# button_peripheral.net
KiCad netlist of a schematic drawn in Altium Designer
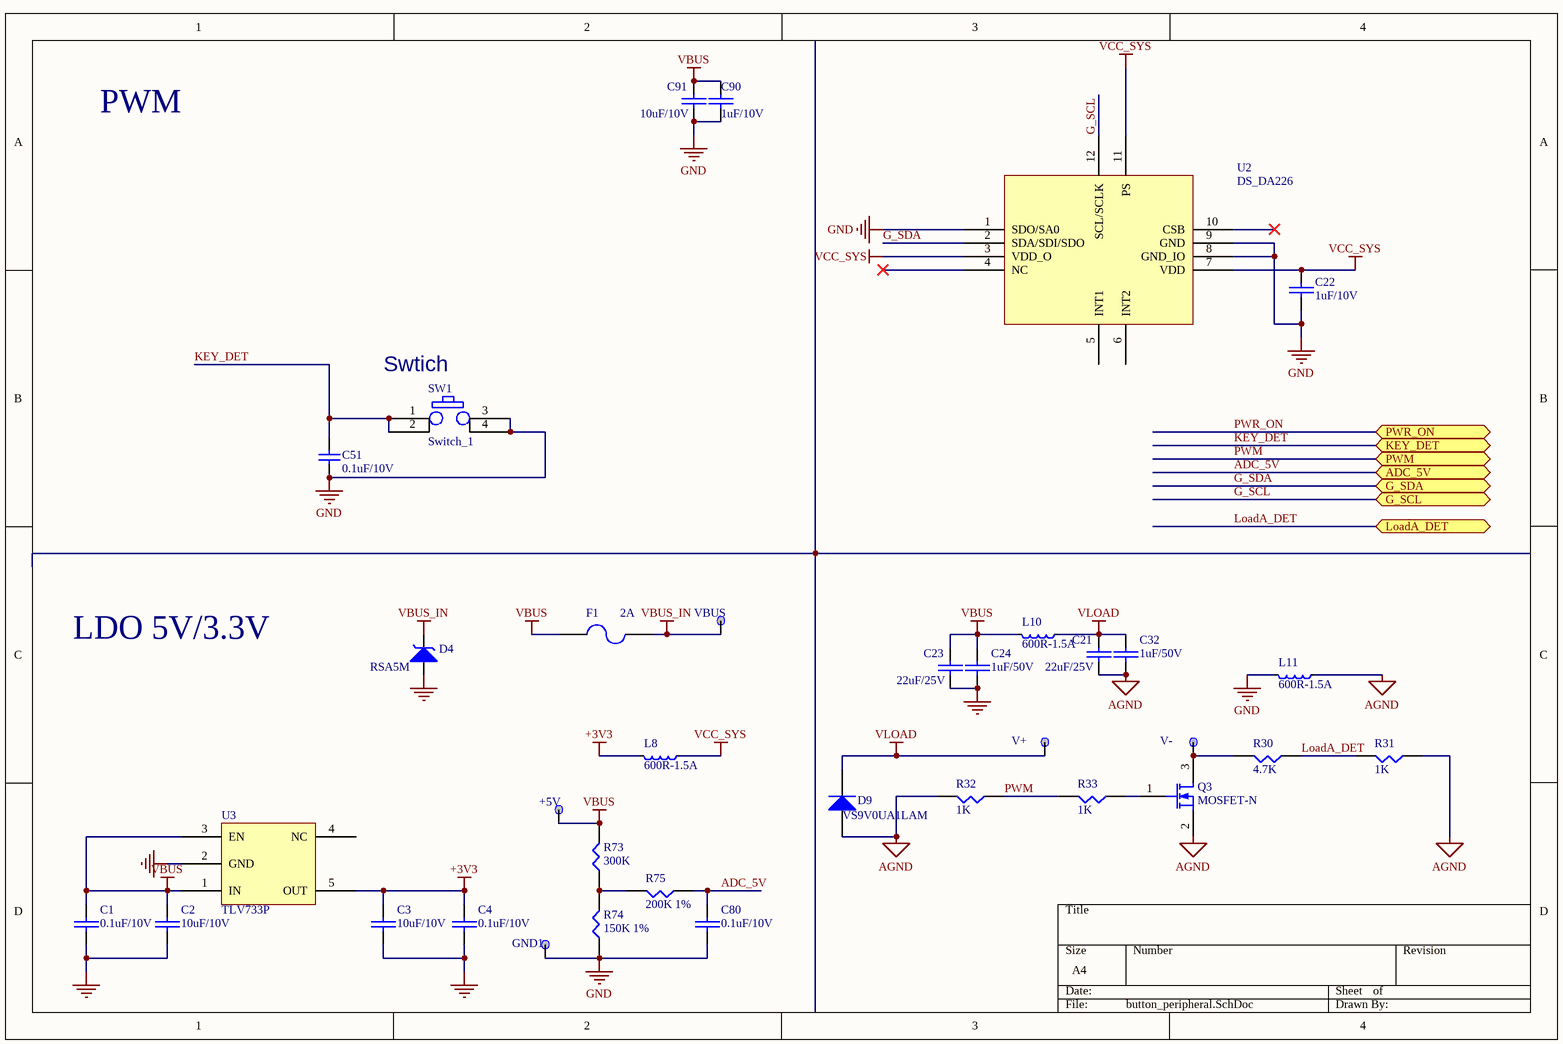
[diagram p0: button_peripheral.SchDoc]

(export (version "E")
  (design (tool "Eeschema 10.0.6"))
  (components
    (comp (ref "+5V") (value "TP") (footprint "TESTPOINT2") (libsource (lib "Almos") (part "TP")))
    (comp (ref "C1")
      (value "0.1uF/10V")
      (footprint "0402C")
      (description "厂家：Murata，型号：GRM155R71A104KA01D")
      (libsource (lib "*") (part "CAP"))
    )
    (comp (ref "C2")
      (value "10uF/10V")
      (footprint "0603C")
      (description "厂家：Murata，型号：GRM188R61A106KE69D")
      (libsource (lib "*") (part "CAP"))
    )
    (comp (ref "C3")
      (value "10uF/10V")
      (footprint "0603C")
      (description "厂家：Murata，型号：GRM188R61A106KE69D")
      (libsource (lib "*") (part "CAP"))
    )
    (comp (ref "C4")
      (value "0.1uF/10V")
      (footprint "0402C")
      (description "厂家：Murata，型号：GRM155R71A104KA01D")
      (libsource (lib "*") (part "CAP"))
    )
    (comp (ref "C21")
      (value "22uF/25V")
      (footprint "0603C")
      (description "厂家：Murata，型号：GRM188R61A106KE69D")
      (libsource (lib "*") (part "CAP"))
    )
    (comp (ref "C22")
      (value "1uF/10V")
      (footprint "0402C")
      (description "厂家：Murata，型号：GRM155R71A104KA01D")
      (libsource (lib "*") (part "CAP"))
    )
    (comp (ref "C23")
      (value "22uF/25V")
      (footprint "0603C")
      (description "厂家：Murata，型号：GRM188R61A106KE69D")
      (libsource (lib "*") (part "CAP"))
    )
    (comp (ref "C24")
      (value "1uF/50V")
      (footprint "0402C")
      (description "厂家：Murata，型号：GRM155R71A104KA01D")
      (libsource (lib "*") (part "CAP"))
    )
    (comp (ref "C32")
      (value "1uF/50V")
      (footprint "0402C")
      (description "厂家：Murata，型号：GRM155R71A104KA01D")
      (libsource (lib "*") (part "CAP"))
    )
    (comp (ref "C51")
      (value "0.1uF/10V")
      (footprint "0402C")
      (description "Capacitor")
      (fields (field (name "PUBLISHER") "Altium Limited"))
      (libsource (lib "Miscellaneous Devices") (part "CAP"))
    )
    (comp (ref "C80")
      (value "0.1uF/10V")
      (footprint "0402C")
      (description "厂家：Murata，型号：GRM155R71A104KA01D")
      (libsource (lib "*") (part "CAP"))
    )
    (comp (ref "C90")
      (value "1uF/10V")
      (footprint "0402C")
      (description "厂家：Murata，型号：GRM188R61A106KE69D")
      (libsource (lib "*") (part "CAP"))
    )
    (comp (ref "C91")
      (value "10uF/10V")
      (footprint "TAN_0603")
      (description "厂家：Murata，型号：GRM188R61A106KE69D")
      (libsource (lib "*") (part "CAP"))
    )
    (comp (ref "D4")
      (value "RSA5M")
      (footprint "SOD-123")
      (description "厂家：ROHM，型号：VMNZC6.8CST2RA")
      (libsource (lib "CCS801 VOC") (part "ESD_1"))
    )
    (comp (ref "D9")
      (value "VS9V0UA1LAM")
      (footprint "SOD_128")
      (description "High Conductance Fast Diode")
      (libsource (lib "Tools") (part "Diode 1N4148"))
    )
    (comp (ref "F1")
      (value "2A")
      (footprint "1206-FUSE - duplicate")
      (description "厂家：万瑞和，型号：smd1206-200")
      (libsource (lib "*") (part "FUSE2"))
    )
    (comp (ref "GND1") (value "TP") (footprint "TESTPOINT_PAD") (libsource (lib "Almos") (part "TP")))
    (comp (ref "L8")
      (value "600R-1.5A")
      (footprint "L_0603")
      (description "High frequency chip inductor ±5%")
      (fields
        (field (name "PART NUMBER") "L0402-27n")
        (field (name "MANUFACTURER") "Murata")
        (field (name "PUBLISHER") "Nordic Semiconductor")
      )
      (libsource (lib "Nordic Passive DB") (part "IND"))
    )
    (comp (ref "L10")
      (value "600R-1.5A")
      (footprint "L_0603")
      (description "High frequency chip inductor ±5%")
      (fields
        (field (name "PART NUMBER") "L0402-27n")
        (field (name "MANUFACTURER") "Murata")
        (field (name "PUBLISHER") "Nordic Semiconductor")
      )
      (libsource (lib "Nordic Passive DB") (part "IND"))
    )
    (comp (ref "L11")
      (value "600R-1.5A")
      (footprint "L_0603")
      (description "High frequency chip inductor ±5%")
      (fields
        (field (name "PART NUMBER") "L0402-27n")
        (field (name "MANUFACTURER") "Murata")
        (field (name "PUBLISHER") "Nordic Semiconductor")
      )
      (libsource (lib "Nordic Passive DB") (part "IND"))
    )
    (comp (ref "Q3")
      (value "MOSFET-N")
      (footprint "TSMT3")
      (description "N-Channel MOSFET")
      (fields (field (name "PUBLISHER") "Altium Limited"))
      (libsource (lib "常用sch库") (part "MOSFET-N"))
    )
    (comp (ref "R30")
      (value "4.7K")
      (footprint "0402R")
      (description "厂家：Yageo，型号：RC0402FR-0720RL")
      (libsource (lib "*") (part "RES1"))
    )
    (comp (ref "R31")
      (value "1K")
      (footprint "0402R")
      (description "厂家：Yageo，型号：RC0402FR-0720RL")
      (libsource (lib "*") (part "RES1"))
    )
    (comp (ref "R32")
      (value "1K")
      (footprint "0402R")
      (description "厂家：Yageo，型号：RC0402FR-0720RL")
      (libsource (lib "*") (part "RES1"))
    )
    (comp (ref "R33")
      (value "1K")
      (footprint "0402R")
      (description "厂家：Yageo，型号：RC0402FR-0720RL")
      (libsource (lib "*") (part "RES1"))
    )
    (comp (ref "R73")
      (value "300K")
      (footprint "0402R")
      (description "厂家：Yageo，型号：RC0402FR-0720RL")
      (libsource (lib "*") (part "RES1"))
    )
    (comp (ref "R74")
      (value "150K 1%")
      (footprint "0402R")
      (description "厂家：Yageo，型号：RC0402FR-0720RL")
      (libsource (lib "*") (part "RES1"))
    )
    (comp (ref "R75")
      (value "200K 1%")
      (footprint "0402R")
      (description "厂家：Yageo，型号：RC0402FR-0720RL")
      (libsource (lib "*") (part "RES1"))
    )
    (comp (ref "SW1")
      (value "Switch_1")
      (footprint "KEY_Panasonic")
      (description "厂家：松下，型号：EVQPLMA15")
      (libsource (lib "Amber_Display") (part "Switch_1"))
    )
    (comp (ref "U2")
      (value "DS_DA226")
      (footprint "LGA-12")
      (description "厂家：ST，型号：LIS2DH12")
      (libsource (lib "Debug Pinborad") (part "LIS2DE12"))
    )
    (comp (ref "U3") (value "TLV733P") (footprint "SOT-23-5") (libsource (lib "Tools") (part "AP3410")))
    (comp (ref "V+") (value "TP") (footprint "TESTPOINT_PAD") (libsource (lib "Almos") (part "TP")))
    (comp (ref "V-") (value "TP") (footprint "TESTPOINT_PAD") (libsource (lib "Almos") (part "TP")))
    (comp (ref "VBUS") (value "TP") (footprint "TESTPOINT_PAD") (libsource (lib "Almos") (part "TP")))
  )
  (nets
    (net (code "1") (name "+3V3") (class "Default")
      (node (ref "C3") (pin "1") (pinfunction "1_1") (pintype "passive"))
      (node (ref "C4") (pin "1") (pinfunction "1_1") (pintype "passive"))
      (node (ref "L8") (pin "2") (pinfunction "2_2") (pintype "passive"))
      (node (ref "U3") (pin "5") (pinfunction "OUT_5") (pintype "passive"))
    )
    (net (code "2") (name "/ADC_5V") (class "Default")
      (node (ref "C80") (pin "1") (pinfunction "1_1") (pintype "passive"))
      (node (ref "R75") (pin "1") (pinfunction "1_1") (pintype "passive"))
    )
    (net (code "3") (name "/G_SCL") (class "Default")
      (node (ref "U2") (pin "12") (pinfunction "SCL/SCLK_12") (pintype "passive"))
    )
    (net (code "4") (name "/G_SDA") (class "Default")
      (node (ref "U2") (pin "2") (pinfunction "SDA/SDI/SDO_2") (pintype "passive"))
    )
    (net (code "5") (name "/KEY_DET") (class "Default")
      (node (ref "C51") (pin "2") (pinfunction "2_2") (pintype "passive"))
      (node (ref "SW1") (pin "1") (pinfunction "1_1") (pintype "passive"))
      (node (ref "SW1") (pin "2") (pinfunction "2_2") (pintype "passive"))
    )
    (net (code "6") (name "/LoadA_DET") (class "Default")
      (node (ref "R30") (pin "1") (pinfunction "1_1") (pintype "passive"))
      (node (ref "R31") (pin "2") (pinfunction "2_2") (pintype "passive"))
    )
    (net (code "7") (name "/PWM") (class "Default")
      (node (ref "R32") (pin "1") (pinfunction "1_1") (pintype "passive"))
      (node (ref "R33") (pin "2") (pinfunction "2_2") (pintype "passive"))
    )
    (net (code "9") (name "AGND") (class "Default")
      (node (ref "C21") (pin "2") (pinfunction "2_2") (pintype "passive"))
      (node (ref "C32") (pin "2") (pinfunction "2_2") (pintype "passive"))
      (node (ref "D9") (pin "2") (pinfunction "A_2") (pintype "passive"))
      (node (ref "L11") (pin "1") (pinfunction "1_1") (pintype "passive"))
      (node (ref "Q3") (pin "2") (pinfunction "S_2") (pintype "passive"))
      (node (ref "R31") (pin "1") (pinfunction "1_1") (pintype "passive"))
      (node (ref "R32") (pin "2") (pinfunction "2_2") (pintype "passive"))
    )
    (net (code "10") (name "GND") (class "Default")
      (node (ref "C1") (pin "2") (pinfunction "2_2") (pintype "passive"))
      (node (ref "C2") (pin "2") (pinfunction "2_2") (pintype "passive"))
      (node (ref "C22") (pin "2") (pinfunction "2_2") (pintype "passive"))
      (node (ref "C23") (pin "2") (pinfunction "2_2") (pintype "passive"))
      (node (ref "C24") (pin "2") (pinfunction "2_2") (pintype "passive"))
      (node (ref "C3") (pin "2") (pinfunction "2_2") (pintype "passive"))
      (node (ref "C4") (pin "2") (pinfunction "2_2") (pintype "passive"))
      (node (ref "C51") (pin "1") (pinfunction "1_1") (pintype "passive"))
      (node (ref "C80") (pin "2") (pinfunction "2_2") (pintype "passive"))
      (node (ref "C90") (pin "2") (pinfunction "2_2") (pintype "passive"))
      (node (ref "C91") (pin "2") (pinfunction "2_2") (pintype "passive"))
      (node (ref "D4") (pin "2") (pinfunction "dIode2_2") (pintype "passive"))
      (node (ref "GND1") (pin "1") (pinfunction "1_1") (pintype "passive"))
      (node (ref "L11") (pin "2") (pinfunction "2_2") (pintype "passive"))
      (node (ref "R74") (pin "1") (pinfunction "1_1") (pintype "passive"))
      (node (ref "SW1") (pin "3") (pinfunction "3_3") (pintype "passive"))
      (node (ref "SW1") (pin "4") (pinfunction "4_4") (pintype "passive"))
      (node (ref "U2") (pin "1") (pinfunction "SDO/SA0_1") (pintype "passive"))
      (node (ref "U2") (pin "8") (pinfunction "GND_IO_8") (pintype "passive"))
      (node (ref "U2") (pin "9") (pinfunction "GND_9") (pintype "passive"))
      (node (ref "U3") (pin "2") (pinfunction "GND_2") (pintype "passive"))
    )
    (net (code "11") (name "Net-(Q3-D)") (class "Default")
      (node (ref "Q3") (pin "3") (pinfunction "D_3") (pintype "passive"))
      (node (ref "R30") (pin "2") (pinfunction "2_2") (pintype "passive"))
      (node (ref "V-") (pin "1") (pinfunction "1_1") (pintype "passive"))
    )
    (net (code "12") (name "Net-(Q3-G)") (class "Default")
      (node (ref "Q3") (pin "1") (pinfunction "G_1") (pintype "passive"))
      (node (ref "R33") (pin "1") (pinfunction "1_1") (pintype "passive"))
    )
    (net (code "13") (name "Net-(R73-Pad1)") (class "Default")
      (node (ref "R73") (pin "1") (pinfunction "1_1") (pintype "passive"))
      (node (ref "R74") (pin "2") (pinfunction "2_2") (pintype "passive"))
      (node (ref "R75") (pin "2") (pinfunction "2_2") (pintype "passive"))
    )
    (net (code "14") (name "VBUS") (class "Default")
      (node (ref "+5V") (pin "1") (pinfunction "1_1") (pintype "passive"))
      (node (ref "C1") (pin "1") (pinfunction "1_1") (pintype "passive"))
      (node (ref "C2") (pin "1") (pinfunction "1_1") (pintype "passive"))
      (node (ref "C23") (pin "1") (pinfunction "1_1") (pintype "passive"))
      (node (ref "C24") (pin "1") (pinfunction "1_1") (pintype "passive"))
      (node (ref "C90") (pin "1") (pinfunction "1_1") (pintype "passive"))
      (node (ref "C91") (pin "1") (pinfunction "1_1") (pintype "passive"))
      (node (ref "F1") (pin "1") (pinfunction "1_1") (pintype "passive"))
      (node (ref "L10") (pin "2") (pinfunction "2_2") (pintype "passive"))
      (node (ref "R73") (pin "2") (pinfunction "2_2") (pintype "passive"))
      (node (ref "U3") (pin "1") (pinfunction "IN_1") (pintype "passive"))
      (node (ref "U3") (pin "3") (pinfunction "EN_3") (pintype "passive"))
    )
    (net (code "15") (name "VBUS_IN") (class "Default")
      (node (ref "D4") (pin "1") (pinfunction "Diode1_1") (pintype "passive"))
      (node (ref "F1") (pin "2") (pinfunction "2_2") (pintype "passive"))
      (node (ref "VBUS") (pin "1") (pinfunction "1_1") (pintype "passive"))
    )
    (net (code "16") (name "VCC_SYS") (class "Default")
      (node (ref "C22") (pin "1") (pinfunction "1_1") (pintype "passive"))
      (node (ref "L8") (pin "1") (pinfunction "1_1") (pintype "passive"))
      (node (ref "U2") (pin "11") (pinfunction "PS_11") (pintype "passive"))
      (node (ref "U2") (pin "3") (pinfunction "VDD_O_3") (pintype "passive"))
      (node (ref "U2") (pin "7") (pinfunction "VDD_7") (pintype "passive"))
    )
    (net (code "17") (name "VLOAD") (class "Default")
      (node (ref "C21") (pin "1") (pinfunction "1_1") (pintype "passive"))
      (node (ref "C32") (pin "1") (pinfunction "1_1") (pintype "passive"))
      (node (ref "D9") (pin "1") (pinfunction "K_1") (pintype "passive"))
      (node (ref "L10") (pin "1") (pinfunction "1_1") (pintype "passive"))
      (node (ref "V+") (pin "1") (pinfunction "1_1") (pintype "passive"))
    )
    (net (code "18") (name "unconnected-(U2-CSB-Pad10)") (class "Default")
      (node (ref "U2") (pin "10") (pinfunction "CSB_10") (pintype "passive+no_connect"))
    )
    (net (code "19") (name "unconnected-(U2-INT1-Pad5)") (class "Default")
      (node (ref "U2") (pin "5") (pinfunction "INT1_5") (pintype "passive"))
    )
    (net (code "20") (name "unconnected-(U2-INT2-Pad6)") (class "Default")
      (node (ref "U2") (pin "6") (pinfunction "INT2_6") (pintype "passive"))
    )
    (net (code "21") (name "unconnected-(U2-NC-Pad4)") (class "Default")
      (node (ref "U2") (pin "4") (pinfunction "NC_4") (pintype "passive+no_connect"))
    )
    (net (code "22") (name "unconnected-(U3-NC-Pad4)") (class "Default")
      (node (ref "U3") (pin "4") (pinfunction "NC_4") (pintype "passive"))
    )
  )
)
